# Xmas_tree.net
KiCad netlist of a schematic drawn in EAGLE
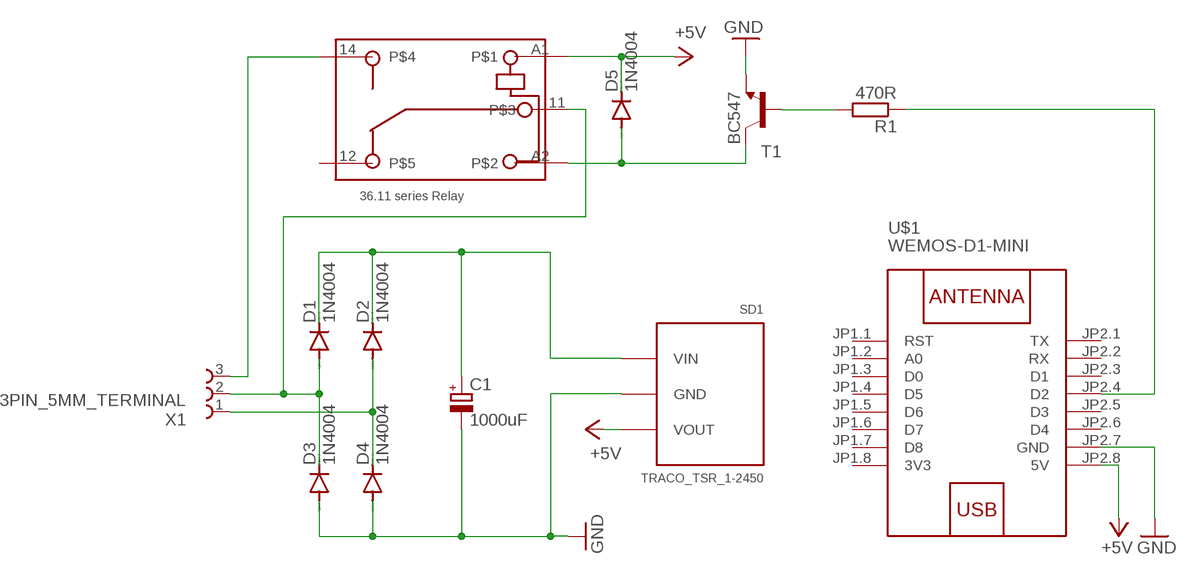
[diagram p0: schematic, sheet 1]

(export (version "E")
  (design (tool "Eeschema 10.0.6"))
  (components
    (comp (ref "C1")
      (value "1000uF")
      (footprint "eagle-import:E3,5-10")
      (libsource (lib "eagle-import") (part "CPOL-EUE3.5-10"))
    )
    (comp (ref "D1")
      (value "1N4004")
      (footprint "eagle-import:DO41-10")
      (libsource (lib "eagle-import") (part "1N4004"))
    )
    (comp (ref "D2")
      (value "1N4004")
      (footprint "eagle-import:DO41-10")
      (libsource (lib "eagle-import") (part "1N4004"))
    )
    (comp (ref "D3")
      (value "1N4004")
      (footprint "eagle-import:DO41-10")
      (libsource (lib "eagle-import") (part "1N4004"))
    )
    (comp (ref "D4")
      (value "1N4004")
      (footprint "eagle-import:DO41-10")
      (libsource (lib "eagle-import") (part "1N4004"))
    )
    (comp (ref "D5")
      (value "1N4004")
      (footprint "eagle-import:DO41-10")
      (libsource (lib "eagle-import") (part "1N4004"))
    )
    (comp (ref "R1")
      (value "470R")
      (footprint "eagle-import:0207_10")
      (libsource (lib "eagle-import") (part "R-EU_0207/10"))
    )
    (comp (ref "RL1")
      (value "36.11")
      (footprint "eagle-import:36.11")
      (libsource (lib "eagle-import") (part "36.11"))
    )
    (comp (ref "SD1")
      (value "TRACO_TSR_1-2450")
      (footprint "eagle-import:TRACO_TSR_1-2450")
      (libsource (lib "eagle-import") (part "TRACO_TSR_1-2450"))
    )
    (comp (ref "T1")
      (value "BC547")
      (footprint "eagle-import:TO92-CBE")
      (libsource (lib "eagle-import") (part "-NPN-TO92-CBEBC547"))
    )
    (comp (ref "U$1")
      (value "WEMOS-D1-MINI")
      (footprint "eagle-import:WEMOS-D1-MINI")
      (libsource (lib "eagle-import") (part "WEMOS-D1-MINI"))
    )
    (comp (ref "X1")
      (value "3PIN_5MM_TERMINAL")
      (footprint "eagle-import:3PIN_5MM_TERMINAL")
      (libsource (lib "eagle-import") (part "3PIN_5MM_TERMINAL"))
    )
  )
  (nets
    (net (code "1") (name "+5V") (class "Default")
      (node (ref "D5") (pin "C") (pinfunction "C_C") (pintype "passive"))
      (node (ref "RL1") (pin "A1") (pinfunction "P$1_A1") (pintype "passive"))
      (node (ref "SD1") (pin "VOUT") (pinfunction "VOUT_VOUT") (pintype "output"))
      (node (ref "U$1") (pin "JP2.8") (pinfunction "5V_JP2.8") (pintype "power_in"))
    )
    (net (code "2") (name "/3V3") (class "Default")
      (node (ref "U$1") (pin "JP1.8") (pinfunction "3V3_JP1.8") (pintype "power_in"))
    )
    (net (code "3") (name "GND") (class "Default")
      (node (ref "C1") (pin "-") (pinfunction "-_-") (pintype "passive"))
      (node (ref "D3") (pin "A") (pinfunction "A_A") (pintype "passive"))
      (node (ref "D4") (pin "A") (pinfunction "A_A") (pintype "passive"))
      (node (ref "SD1") (pin "GND") (pinfunction "GND_GND") (pintype "bidirectional"))
      (node (ref "T1") (pin "E") (pinfunction "E_E") (pintype "passive"))
      (node (ref "U$1") (pin "JP2.7") (pinfunction "GND_JP2.7") (pintype "power_in"))
    )
    (net (code "4") (name "Net-(C1-Pad+)") (class "Default")
      (node (ref "C1") (pin "+") (pinfunction "+_+") (pintype "passive"))
      (node (ref "D1") (pin "C") (pinfunction "C_C") (pintype "passive"))
      (node (ref "D2") (pin "C") (pinfunction "C_C") (pintype "passive"))
      (node (ref "SD1") (pin "VIN") (pinfunction "VIN_VIN") (pintype "input"))
    )
    (net (code "5") (name "Net-(D2-PadA)") (class "Default")
      (node (ref "D2") (pin "A") (pinfunction "A_A") (pintype "passive"))
      (node (ref "D4") (pin "C") (pinfunction "C_C") (pintype "passive"))
      (node (ref "X1") (pin "1") (pinfunction "1_1") (pintype "passive"))
    )
    (net (code "6") (name "Net-(R1-Pad2)") (class "Default")
      (node (ref "R1") (pin "2") (pinfunction "2_2") (pintype "passive"))
      (node (ref "T1") (pin "B") (pinfunction "B_B") (pintype "passive"))
    )
    (net (code "7") (name "Net-(RL1-P$2)") (class "Default")
      (node (ref "D5") (pin "A") (pinfunction "A_A") (pintype "passive"))
      (node (ref "RL1") (pin "A2") (pinfunction "P$2_A2") (pintype "passive"))
      (node (ref "T1") (pin "C") (pinfunction "C_C") (pintype "passive"))
    )
    (net (code "8") (name "Net-(RL1-P$3)") (class "Default")
      (node (ref "D1") (pin "A") (pinfunction "A_A") (pintype "passive"))
      (node (ref "D3") (pin "C") (pinfunction "C_C") (pintype "passive"))
      (node (ref "RL1") (pin "11") (pinfunction "P$3_11") (pintype "passive"))
      (node (ref "X1") (pin "2") (pinfunction "2_2") (pintype "passive"))
    )
    (net (code "9") (name "Net-(RL1-P$4)") (class "Default")
      (node (ref "RL1") (pin "14") (pinfunction "P$4_14") (pintype "passive"))
      (node (ref "X1") (pin "3") (pinfunction "3_3") (pintype "passive"))
    )
    (net (code "10") (name "Net-(U$1-D2)") (class "Default")
      (node (ref "R1") (pin "1") (pinfunction "1_1") (pintype "passive"))
      (node (ref "U$1") (pin "JP2.4") (pinfunction "D2_JP2.4") (pintype "bidirectional"))
    )
    (net (code "11") (name "unconnected-(RL1-P$5-Pad12)") (class "Default")
      (node (ref "RL1") (pin "12") (pinfunction "P$5_12") (pintype "passive"))
    )
    (net (code "12") (name "unconnected-(U$1-A0-PadJP1.2)") (class "Default")
      (node (ref "U$1") (pin "JP1.2") (pinfunction "A0_JP1.2") (pintype "bidirectional"))
    )
    (net (code "13") (name "unconnected-(U$1-D0-PadJP1.3)") (class "Default")
      (node (ref "U$1") (pin "JP1.3") (pinfunction "D0_JP1.3") (pintype "bidirectional"))
    )
    (net (code "14") (name "unconnected-(U$1-D1-PadJP2.3)") (class "Default")
      (node (ref "U$1") (pin "JP2.3") (pinfunction "D1_JP2.3") (pintype "bidirectional"))
    )
    (net (code "15") (name "unconnected-(U$1-D3-PadJP2.5)") (class "Default")
      (node (ref "U$1") (pin "JP2.5") (pinfunction "D3_JP2.5") (pintype "bidirectional"))
    )
    (net (code "16") (name "unconnected-(U$1-D4-PadJP2.6)") (class "Default")
      (node (ref "U$1") (pin "JP2.6") (pinfunction "D4_JP2.6") (pintype "bidirectional"))
    )
    (net (code "17") (name "unconnected-(U$1-D5-PadJP1.4)") (class "Default")
      (node (ref "U$1") (pin "JP1.4") (pinfunction "D5_JP1.4") (pintype "bidirectional"))
    )
    (net (code "18") (name "unconnected-(U$1-D6-PadJP1.5)") (class "Default")
      (node (ref "U$1") (pin "JP1.5") (pinfunction "D6_JP1.5") (pintype "bidirectional"))
    )
    (net (code "19") (name "unconnected-(U$1-D7-PadJP1.6)") (class "Default")
      (node (ref "U$1") (pin "JP1.6") (pinfunction "D7_JP1.6") (pintype "bidirectional"))
    )
    (net (code "20") (name "unconnected-(U$1-D8-PadJP1.7)") (class "Default")
      (node (ref "U$1") (pin "JP1.7") (pinfunction "D8_JP1.7") (pintype "bidirectional"))
    )
    (net (code "21") (name "unconnected-(U$1-RST-PadJP1.1)") (class "Default")
      (node (ref "U$1") (pin "JP1.1") (pinfunction "RST_JP1.1") (pintype "bidirectional"))
    )
    (net (code "22") (name "unconnected-(U$1-RX-PadJP2.2)") (class "Default")
      (node (ref "U$1") (pin "JP2.2") (pinfunction "RX_JP2.2") (pintype "bidirectional"))
    )
    (net (code "23") (name "unconnected-(U$1-TX-PadJP2.1)") (class "Default")
      (node (ref "U$1") (pin "JP2.1") (pinfunction "TX_JP2.1") (pintype "bidirectional"))
    )
  )
)
